# untitled.net
KiCad netlist of a schematic drawn in EAGLE
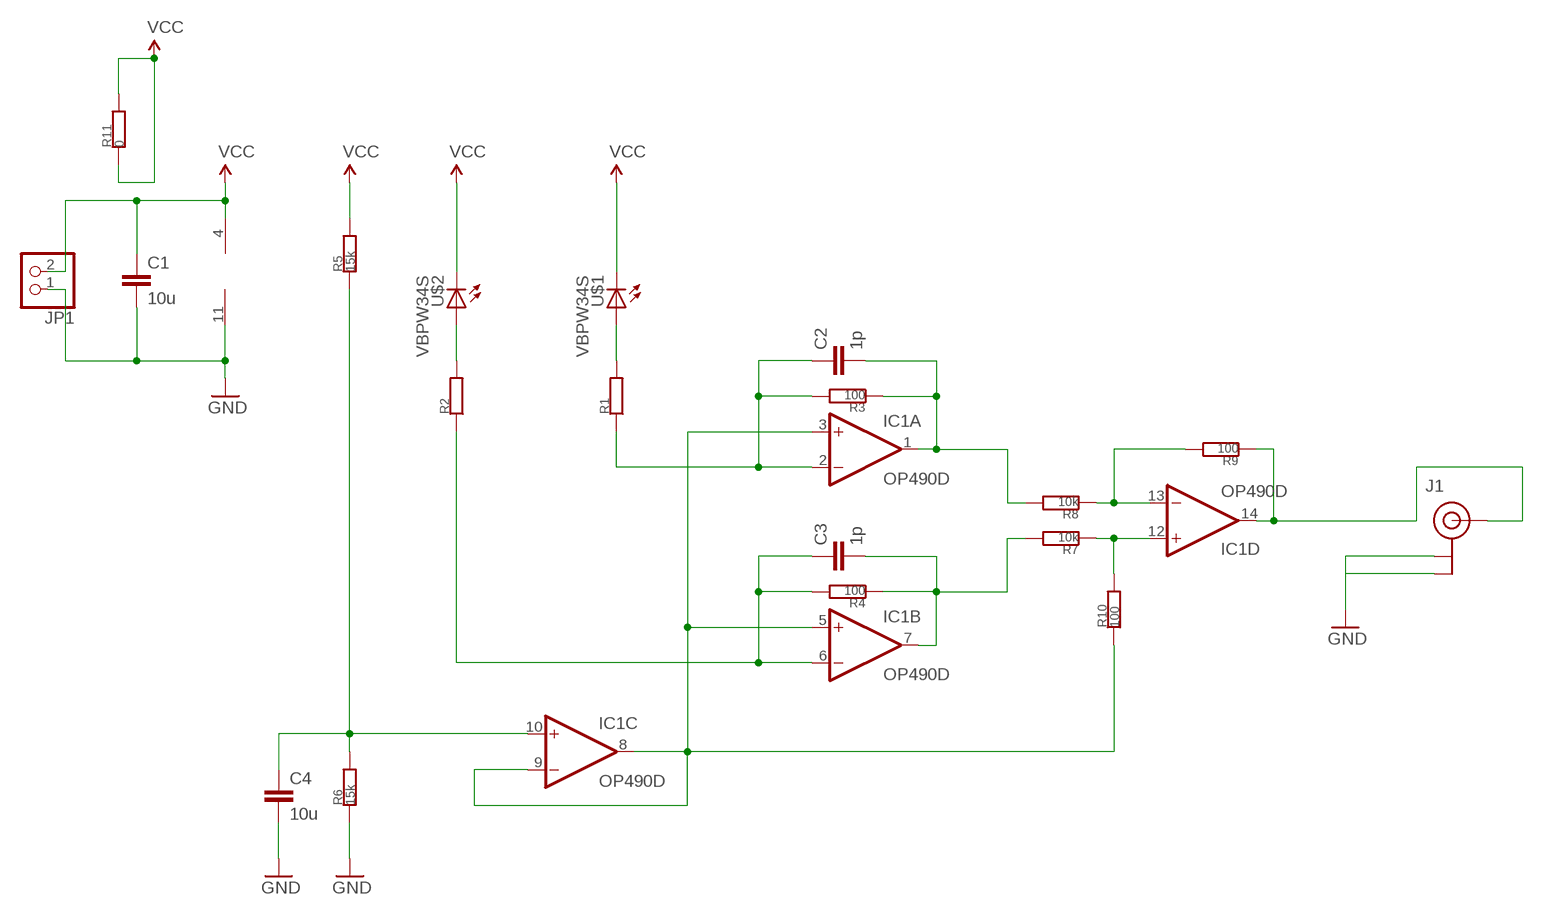
[diagram p0: schematic, sheet 1]

(export (version "E")
  (design (tool "Eeschema 10.0.6"))
  (components
    (comp (ref "C1")
      (value "10u")
      (footprint "eagle-import:C0805")
      (libsource (lib "eagle-import") (part "CC0805"))
    )
    (comp (ref "C2")
      (value "1p")
      (footprint "eagle-import:C0603")
      (libsource (lib "eagle-import") (part "CC0603"))
    )
    (comp (ref "C3")
      (value "1p")
      (footprint "eagle-import:C0603")
      (libsource (lib "eagle-import") (part "CC0603"))
    )
    (comp (ref "C4")
      (value "10u")
      (footprint "eagle-import:C0805")
      (libsource (lib "eagle-import") (part "CC0805"))
    )
    (comp (ref "IC1")
      (value "OP490D")
      (footprint "eagle-import:SO14")
      (libsource (lib "eagle-import") (part "OP490D"))
    )
    (comp (ref "J1")
      (value "U.FL")
      (footprint "eagle-import:U.FL")
      (libsource (lib "eagle-import") (part "U.FL"))
    )
    (comp (ref "JP1")
      (value "PINHD-1X2")
      (footprint "eagle-import:1X02")
      (libsource (lib "eagle-import") (part "PINHD-1X2"))
    )
    (comp (ref "R1")
      (value "R0603")
      (footprint "eagle-import:0603")
      (libsource (lib "eagle-import") (part "R0603"))
    )
    (comp (ref "R2")
      (value "R0603")
      (footprint "eagle-import:0603")
      (libsource (lib "eagle-import") (part "R0603"))
    )
    (comp (ref "R3")
      (value "100")
      (footprint "eagle-import:0603")
      (libsource (lib "eagle-import") (part "R0603"))
    )
    (comp (ref "R4")
      (value "100")
      (footprint "eagle-import:0603")
      (libsource (lib "eagle-import") (part "R0603"))
    )
    (comp (ref "R5")
      (value "15k")
      (footprint "eagle-import:0603")
      (libsource (lib "eagle-import") (part "R0603"))
    )
    (comp (ref "R6")
      (value "15k")
      (footprint "eagle-import:0603")
      (libsource (lib "eagle-import") (part "R0603"))
    )
    (comp (ref "R7")
      (value "10k")
      (footprint "eagle-import:0603")
      (libsource (lib "eagle-import") (part "R0603"))
    )
    (comp (ref "R8")
      (value "10k")
      (footprint "eagle-import:0603")
      (libsource (lib "eagle-import") (part "R0603"))
    )
    (comp (ref "R9")
      (value "100")
      (footprint "eagle-import:0603")
      (libsource (lib "eagle-import") (part "R0603"))
    )
    (comp (ref "R10")
      (value "100")
      (footprint "eagle-import:0603")
      (libsource (lib "eagle-import") (part "R0603"))
    )
    (comp (ref "R11")
      (value "0")
      (footprint "eagle-import:0603")
      (libsource (lib "eagle-import") (part "R0603"))
    )
    (comp (ref "U$1")
      (value "VBPW34S")
      (footprint "eagle-import:SMD_PIN")
      (libsource (lib "eagle-import") (part "VBPW34S"))
    )
    (comp (ref "U$2")
      (value "VBPW34S")
      (footprint "eagle-import:SMD_PIN")
      (libsource (lib "eagle-import") (part "VBPW34S"))
    )
  )
  (nets
    (net (code "1") (name "GND") (class "Default")
      (node (ref "C1") (pin "2") (pinfunction "2_2") (pintype "passive"))
      (node (ref "C4") (pin "2") (pinfunction "2_2") (pintype "passive"))
      (node (ref "IC1") (pin "11") (pinfunction "V-_11") (pintype "power_in"))
      (node (ref "J1") (pin "P$1") (pinfunction "GND_P$1") (pintype "bidirectional"))
      (node (ref "J1") (pin "P$2") (pinfunction "GND_P$2") (pintype "bidirectional"))
      (node (ref "JP1") (pin "1") (pinfunction "1_1") (pintype "passive"))
      (node (ref "R6") (pin "1") (pinfunction "1_1") (pintype "passive"))
    )
    (net (code "2") (name "Net-(IC1A-+IN)") (class "Default")
      (node (ref "IC1") (pin "3") (pinfunction "+IN_3") (pintype "input"))
      (node (ref "IC1") (pin "5") (pinfunction "+IN_5") (pintype "input"))
      (node (ref "IC1") (pin "8") (pinfunction "OUT_8") (pintype "output"))
      (node (ref "IC1") (pin "9") (pinfunction "-IN_9") (pintype "input"))
      (node (ref "R10") (pin "1") (pinfunction "1_1") (pintype "passive"))
    )
    (net (code "3") (name "Net-(IC1A--IN)") (class "Default")
      (node (ref "C2") (pin "1") (pinfunction "1_1") (pintype "passive"))
      (node (ref "IC1") (pin "2") (pinfunction "-IN_2") (pintype "input"))
      (node (ref "R1") (pin "1") (pinfunction "1_1") (pintype "passive"))
      (node (ref "R3") (pin "2") (pinfunction "2_2") (pintype "passive"))
    )
    (net (code "4") (name "Net-(IC1A-OUT)") (class "Default")
      (node (ref "C2") (pin "2") (pinfunction "2_2") (pintype "passive"))
      (node (ref "IC1") (pin "1") (pinfunction "OUT_1") (pintype "output"))
      (node (ref "R3") (pin "1") (pinfunction "1_1") (pintype "passive"))
      (node (ref "R8") (pin "2") (pinfunction "2_2") (pintype "passive"))
    )
    (net (code "5") (name "Net-(IC1B--IN)") (class "Default")
      (node (ref "C3") (pin "1") (pinfunction "1_1") (pintype "passive"))
      (node (ref "IC1") (pin "6") (pinfunction "-IN_6") (pintype "input"))
      (node (ref "R2") (pin "1") (pinfunction "1_1") (pintype "passive"))
      (node (ref "R4") (pin "2") (pinfunction "2_2") (pintype "passive"))
    )
    (net (code "6") (name "Net-(IC1B-OUT)") (class "Default")
      (node (ref "C3") (pin "2") (pinfunction "2_2") (pintype "passive"))
      (node (ref "IC1") (pin "7") (pinfunction "OUT_7") (pintype "output"))
      (node (ref "R4") (pin "1") (pinfunction "1_1") (pintype "passive"))
      (node (ref "R7") (pin "2") (pinfunction "2_2") (pintype "passive"))
    )
    (net (code "7") (name "Net-(IC1C-+IN)") (class "Default")
      (node (ref "C4") (pin "1") (pinfunction "1_1") (pintype "passive"))
      (node (ref "IC1") (pin "10") (pinfunction "+IN_10") (pintype "input"))
      (node (ref "R5") (pin "1") (pinfunction "1_1") (pintype "passive"))
      (node (ref "R6") (pin "2") (pinfunction "2_2") (pintype "passive"))
    )
    (net (code "8") (name "Net-(IC1D-+IN)") (class "Default")
      (node (ref "IC1") (pin "12") (pinfunction "+IN_12") (pintype "input"))
      (node (ref "R10") (pin "2") (pinfunction "2_2") (pintype "passive"))
      (node (ref "R7") (pin "1") (pinfunction "1_1") (pintype "passive"))
    )
    (net (code "9") (name "Net-(IC1D--IN)") (class "Default")
      (node (ref "IC1") (pin "13") (pinfunction "-IN_13") (pintype "input"))
      (node (ref "R8") (pin "1") (pinfunction "1_1") (pintype "passive"))
      (node (ref "R9") (pin "2") (pinfunction "2_2") (pintype "passive"))
    )
    (net (code "10") (name "Net-(IC1D-OUT)") (class "Default")
      (node (ref "IC1") (pin "14") (pinfunction "OUT_14") (pintype "output"))
      (node (ref "J1") (pin "P$3") (pinfunction "SIGNAL_P$3") (pintype "bidirectional"))
      (node (ref "R9") (pin "1") (pinfunction "1_1") (pintype "passive"))
    )
    (net (code "11") (name "Net-(R1-Pad2)") (class "Default")
      (node (ref "R1") (pin "2") (pinfunction "2_2") (pintype "passive"))
      (node (ref "U$1") (pin "A") (pinfunction "A_A") (pintype "passive"))
    )
    (net (code "12") (name "Net-(R2-Pad2)") (class "Default")
      (node (ref "R2") (pin "2") (pinfunction "2_2") (pintype "passive"))
      (node (ref "U$2") (pin "A") (pinfunction "A_A") (pintype "passive"))
    )
    (net (code "13") (name "VCC") (class "Default")
      (node (ref "C1") (pin "1") (pinfunction "1_1") (pintype "passive"))
      (node (ref "IC1") (pin "4") (pinfunction "V+_4") (pintype "power_in"))
      (node (ref "JP1") (pin "2") (pinfunction "2_2") (pintype "passive"))
      (node (ref "R11") (pin "1") (pinfunction "1_1") (pintype "passive"))
      (node (ref "R11") (pin "2") (pinfunction "2_2") (pintype "passive"))
      (node (ref "R5") (pin "2") (pinfunction "2_2") (pintype "passive"))
      (node (ref "U$1") (pin "K") (pinfunction "C_K") (pintype "passive"))
      (node (ref "U$2") (pin "K") (pinfunction "C_K") (pintype "passive"))
    )
  )
)
